# Telemetry.net
KiCad netlist of a schematic drawn in Altium Designer
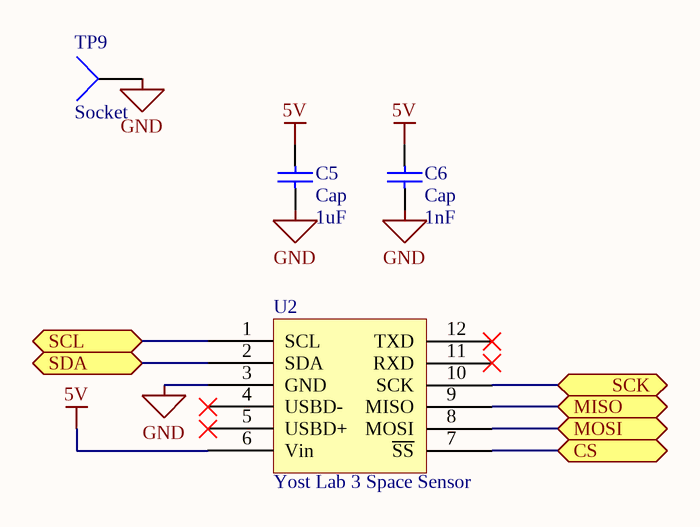
[diagram p0: Telemetry.SchDoc]

(export (version "E")
  (design (tool "Eeschema 10.0.6"))
  (components
    (comp (ref "C5")
      (value "Cap")
      (footprint "RESC3116X65N")
      (description "Capacitor")
      (fields
        (field (name "ALTIUM_VALUE") "1uF")
        (field (name "MANUFACTURER PART NUMBER") "CL31B105KCHNNNE")
        (field (name "VENDOR PART NUMBER") "1276-1838-1-ND")
      )
      (libsource (lib "Miscellaneous Devices") (part "Cap"))
    )
    (comp (ref "C6")
      (value "Cap")
      (footprint "0402")
      (description "Capacitor")
      (fields
        (field (name "ALTIUM_VALUE") "1nF")
        (field (name "MANUFACTURER PART NUMBER") "GRM155R72A102KA01D")
        (field (name "VENDOR PART NUMBER") "490-6366-1-ND")
      )
      (libsource (lib "Miscellaneous Devices") (part "Cap"))
    )
    (comp (ref "TP9")
      (value "Socket")
      (footprint "5006")
      (fields
        (field (name "MANUFACTURER PART NUMBER") "5006")
        (field (name "VENDOR PART NUMBER") "36-5006-ND")
        (field (name "PUBLISHER") "Altium Limited")
      )
      (libsource (lib "Miscellaneous Connectors") (part "Socket"))
    )
    (comp (ref "U2")
      (value "Yost Lab 3 Space Sensor")
      (footprint "Yost 3 Space Sensor")
      (libsource (lib "BeagleCape") (part "Yost Lab 3 Space Sensor"))
    )
  )
  (nets
    (net (code "1") (name "/CS") (class "Default")
      (node (ref "U2") (pin "7") (pinfunction "~{SS}_7") (pintype "passive"))
    )
    (net (code "2") (name "/MISO") (class "Default")
      (node (ref "U2") (pin "9") (pinfunction "MISO_9") (pintype "passive"))
    )
    (net (code "3") (name "/MOSI") (class "Default")
      (node (ref "U2") (pin "8") (pinfunction "MOSI_8") (pintype "passive"))
    )
    (net (code "4") (name "/SCK") (class "Default")
      (node (ref "U2") (pin "10") (pinfunction "SCK_10") (pintype "passive"))
    )
    (net (code "5") (name "/SCL") (class "Default")
      (node (ref "U2") (pin "1") (pinfunction "SCL_1") (pintype "passive"))
    )
    (net (code "6") (name "/SDA") (class "Default")
      (node (ref "U2") (pin "2") (pinfunction "SDA_2") (pintype "passive"))
    )
    (net (code "7") (name "5V") (class "Default")
      (node (ref "C5") (pin "2") (pinfunction "2_2") (pintype "passive"))
      (node (ref "C6") (pin "2") (pinfunction "2_2") (pintype "passive"))
      (node (ref "U2") (pin "6") (pinfunction "Vin_6") (pintype "passive"))
    )
    (net (code "8") (name "GND") (class "Default")
      (node (ref "C5") (pin "1") (pinfunction "1_1") (pintype "passive"))
      (node (ref "C6") (pin "1") (pinfunction "1_1") (pintype "passive"))
      (node (ref "TP9") (pin "1") (pinfunction "1_1") (pintype "passive"))
      (node (ref "U2") (pin "3") (pinfunction "GND_3") (pintype "passive"))
    )
    (net (code "9") (name "unconnected-(U2-RXD-Pad11)") (class "Default")
      (node (ref "U2") (pin "11") (pinfunction "RXD_11") (pintype "passive+no_connect"))
    )
    (net (code "10") (name "unconnected-(U2-TXD-Pad12)") (class "Default")
      (node (ref "U2") (pin "12") (pinfunction "TXD_12") (pintype "passive+no_connect"))
    )
    (net (code "11") (name "unconnected-(U2-USBD+-Pad5)") (class "Default")
      (node (ref "U2") (pin "5") (pinfunction "USBD+_5") (pintype "passive+no_connect"))
    )
    (net (code "12") (name "unconnected-(U2-USBD--Pad4)") (class "Default")
      (node (ref "U2") (pin "4") (pinfunction "USBD-_4") (pintype "passive+no_connect"))
    )
  )
)
